# RunnersHighEA_main.net
KiCad netlist of a schematic drawn in EAGLE
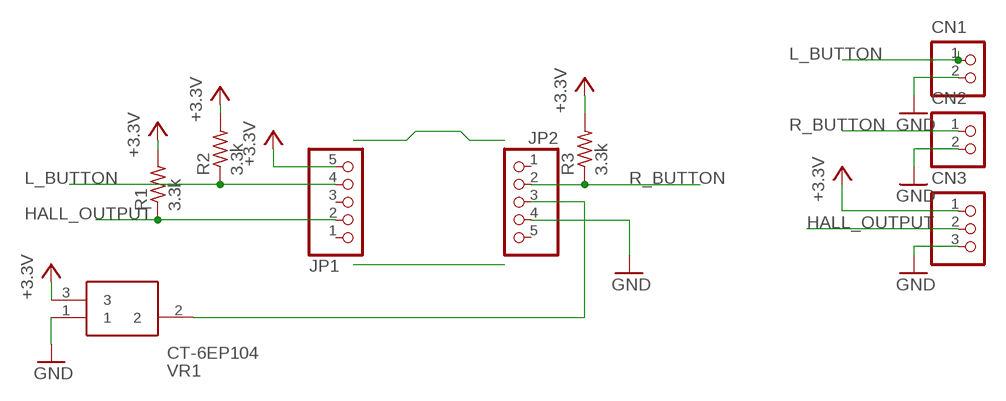
[diagram p0: schematic, sheet 1]

(export (version "E")
  (design (tool "Eeschema 10.0.6"))
  (components
    (comp (ref "CN1")
      (value "S2B-PH-SM4-TB")
      (footprint "eagle-import:S2B-PH-SM4-TB")
      (libsource (lib "eagle-import") (part "S2B-PH-SM4-TB"))
    )
    (comp (ref "CN2")
      (value "S2B-PH-SM4-TB")
      (footprint "eagle-import:S2B-PH-SM4-TB")
      (libsource (lib "eagle-import") (part "S2B-PH-SM4-TB"))
    )
    (comp (ref "CN3")
      (value "S3B-PH-SM4-TB")
      (footprint "eagle-import:S3B-PH-SM4-TB")
      (libsource (lib "eagle-import") (part "S3B-PH-SM4-TB"))
    )
    (comp (ref "JP1")
      (value "PINHD-1X5")
      (footprint "eagle-import:1X05")
      (libsource (lib "eagle-import") (part "PINHD-1X5"))
    )
    (comp (ref "JP2")
      (value "PINHD-1X5")
      (footprint "eagle-import:1X05")
      (libsource (lib "eagle-import") (part "PINHD-1X5"))
    )
    (comp (ref "R1")
      (value "3.3k")
      (footprint "eagle-import:R0603")
      (libsource (lib "eagle-import") (part "R-US_R0603"))
    )
    (comp (ref "R2")
      (value "3.3k")
      (footprint "eagle-import:R0603")
      (libsource (lib "eagle-import") (part "R-US_R0603"))
    )
    (comp (ref "R3")
      (value "3.3k")
      (footprint "eagle-import:R0603")
      (libsource (lib "eagle-import") (part "R-US_R0603"))
    )
    (comp (ref "VR1")
      (value "CT-6EP104")
      (footprint "eagle-import:CT-6EP")
      (libsource (lib "eagle-import") (part "CT-6EP104"))
    )
  )
  (nets
    (net (code "1") (name "+3.3V") (class "Default")
      (node (ref "CN3") (pin "1") (pinfunction "1_1") (pintype "passive"))
      (node (ref "JP1") (pin "5") (pinfunction "5_5") (pintype "passive"))
      (node (ref "R1") (pin "2") (pinfunction "2_2") (pintype "passive"))
      (node (ref "R2") (pin "2") (pinfunction "2_2") (pintype "passive"))
      (node (ref "R3") (pin "2") (pinfunction "2_2") (pintype "passive"))
      (node (ref "VR1") (pin "3") (pinfunction "3_3") (pintype "bidirectional"))
    )
    (net (code "2") (name "/HALL_OUTPUT") (class "Default")
      (node (ref "CN3") (pin "2") (pinfunction "2_2") (pintype "passive"))
      (node (ref "JP1") (pin "2") (pinfunction "2_2") (pintype "passive"))
      (node (ref "R1") (pin "1") (pinfunction "1_1") (pintype "passive"))
    )
    (net (code "3") (name "/L_BUTTON") (class "Default")
      (node (ref "CN1") (pin "1") (pinfunction "1_1") (pintype "passive"))
      (node (ref "JP1") (pin "4") (pinfunction "4_4") (pintype "passive"))
      (node (ref "R2") (pin "1") (pinfunction "1_1") (pintype "passive"))
    )
    (net (code "4") (name "/R_BUTTON") (class "Default")
      (node (ref "CN2") (pin "1") (pinfunction "1_1") (pintype "passive"))
      (node (ref "JP2") (pin "2") (pinfunction "2_2") (pintype "passive"))
      (node (ref "R3") (pin "1") (pinfunction "1_1") (pintype "passive"))
    )
    (net (code "5") (name "GND") (class "Default")
      (node (ref "CN1") (pin "2") (pinfunction "2_2") (pintype "passive"))
      (node (ref "CN2") (pin "2") (pinfunction "2_2") (pintype "passive"))
      (node (ref "CN3") (pin "3") (pinfunction "3_3") (pintype "passive"))
      (node (ref "JP2") (pin "4") (pinfunction "4_4") (pintype "passive"))
      (node (ref "VR1") (pin "1") (pinfunction "1_1") (pintype "bidirectional"))
    )
    (net (code "6") (name "Net-(JP2-Pad3)") (class "Default")
      (node (ref "JP2") (pin "3") (pinfunction "3_3") (pintype "passive"))
      (node (ref "VR1") (pin "2") (pinfunction "2_2") (pintype "bidirectional"))
    )
    (net (code "7") (name "unconnected-(JP1-Pad1)") (class "Default")
      (node (ref "JP1") (pin "1") (pinfunction "1_1") (pintype "passive"))
    )
    (net (code "8") (name "unconnected-(JP1-Pad3)") (class "Default")
      (node (ref "JP1") (pin "3") (pinfunction "3_3") (pintype "passive"))
    )
    (net (code "9") (name "unconnected-(JP2-Pad1)") (class "Default")
      (node (ref "JP2") (pin "1") (pinfunction "1_1") (pintype "passive"))
    )
    (net (code "10") (name "unconnected-(JP2-Pad5)") (class "Default")
      (node (ref "JP2") (pin "5") (pinfunction "5_5") (pintype "passive"))
    )
  )
)
